# Register.net
KiCad netlist of a schematic drawn in EAGLE
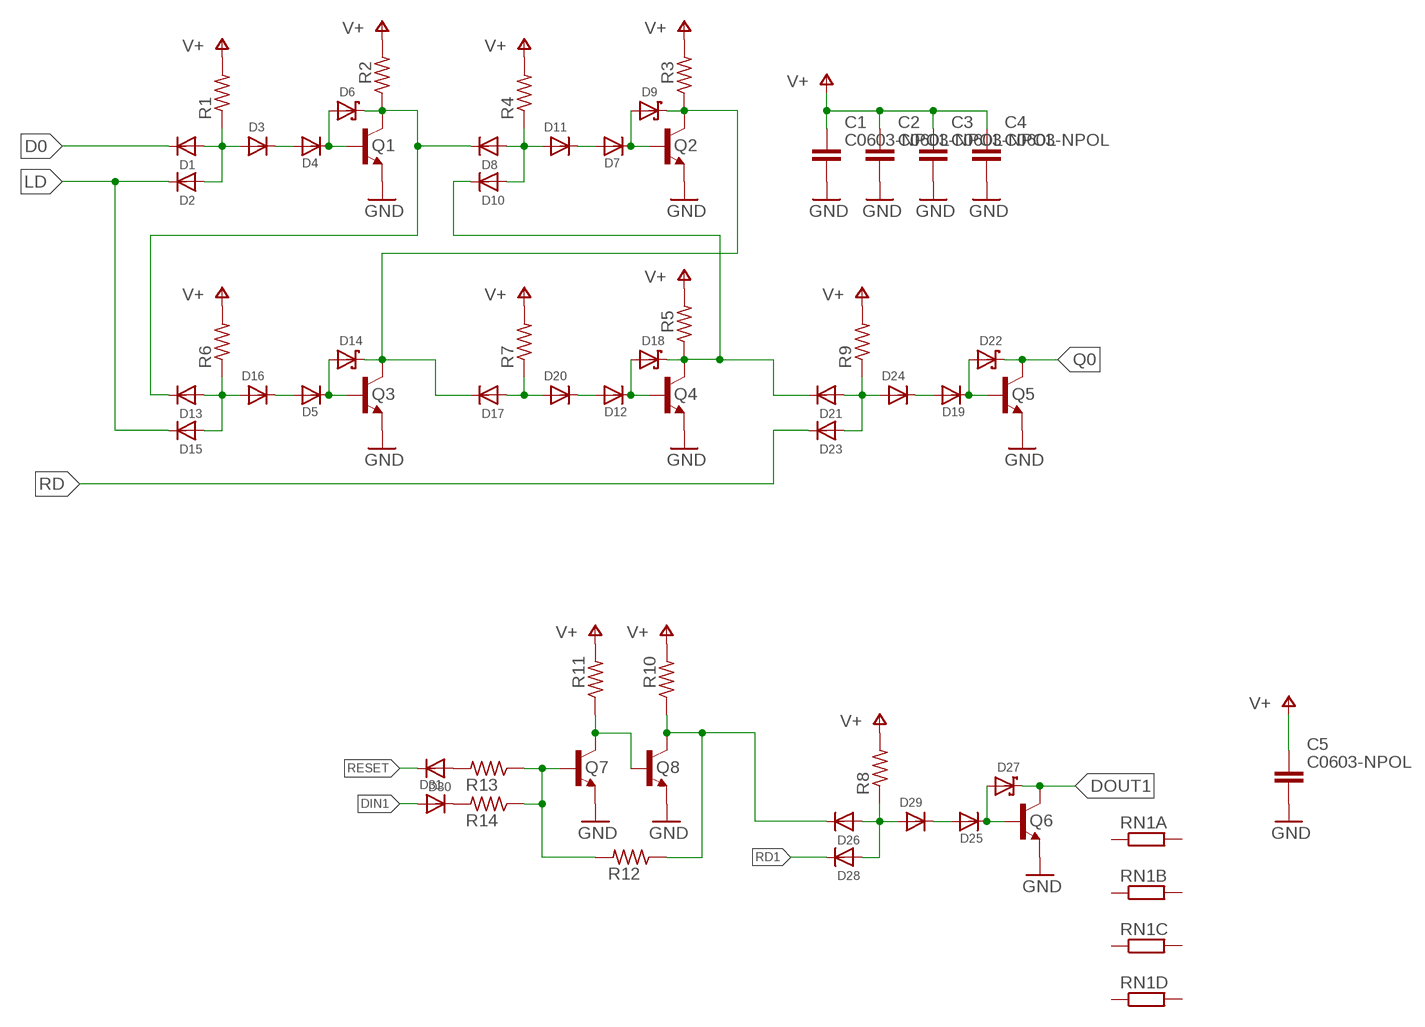
[diagram p0: schematic, sheet 1]

(export (version "E")
  (design (tool "Eeschema 10.0.6"))
  (components
    (comp (ref "C1")
      (value "C0603-NPOL")
      (footprint "eagle-import:C0603")
      (libsource (lib "eagle-import") (part "C0603-NPOL"))
    )
    (comp (ref "C2")
      (value "C0603-NPOL")
      (footprint "eagle-import:C0603")
      (libsource (lib "eagle-import") (part "C0603-NPOL"))
    )
    (comp (ref "C3")
      (value "C0603-NPOL")
      (footprint "eagle-import:C0603")
      (libsource (lib "eagle-import") (part "C0603-NPOL"))
    )
    (comp (ref "C4")
      (value "C0603-NPOL")
      (footprint "eagle-import:C0603")
      (libsource (lib "eagle-import") (part "C0603-NPOL"))
    )
    (comp (ref "C5")
      (value "C0603-NPOL")
      (footprint "eagle-import:C0603")
      (libsource (lib "eagle-import") (part "C0603-NPOL"))
    )
    (comp (ref "D1")
      (value "DIODE-SOD323")
      (footprint "eagle-import:SOD323F")
      (libsource (lib "eagle-import") (part "DIODE-SOD323"))
    )
    (comp (ref "D2")
      (value "DIODE-SOD323")
      (footprint "eagle-import:SOD323F")
      (libsource (lib "eagle-import") (part "DIODE-SOD323"))
    )
    (comp (ref "D3")
      (value "DIODE-SOD323")
      (footprint "eagle-import:SOD323F")
      (libsource (lib "eagle-import") (part "DIODE-SOD323"))
    )
    (comp (ref "D4")
      (value "DIODE-SOD323")
      (footprint "eagle-import:SOD323F")
      (libsource (lib "eagle-import") (part "DIODE-SOD323"))
    )
    (comp (ref "D5")
      (value "DIODE-SOD323")
      (footprint "eagle-import:SOD323F")
      (libsource (lib "eagle-import") (part "DIODE-SOD323"))
    )
    (comp (ref "D6")
      (value "SCHOTTKYSOT323")
      (footprint "eagle-import:SOT23")
      (libsource (lib "eagle-import") (part "SCHOTTKYSOT323"))
    )
    (comp (ref "D7")
      (value "DIODE-SOD323")
      (footprint "eagle-import:SOD323F")
      (libsource (lib "eagle-import") (part "DIODE-SOD323"))
    )
    (comp (ref "D8")
      (value "DIODE-SOD323")
      (footprint "eagle-import:SOD323F")
      (libsource (lib "eagle-import") (part "DIODE-SOD323"))
    )
    (comp (ref "D9")
      (value "SCHOTTKYSOT323")
      (footprint "eagle-import:SOT23")
      (libsource (lib "eagle-import") (part "SCHOTTKYSOT323"))
    )
    (comp (ref "D10")
      (value "DIODE-SOD323")
      (footprint "eagle-import:SOD323F")
      (libsource (lib "eagle-import") (part "DIODE-SOD323"))
    )
    (comp (ref "D11")
      (value "DIODE-SOD323")
      (footprint "eagle-import:SOD323F")
      (libsource (lib "eagle-import") (part "DIODE-SOD323"))
    )
    (comp (ref "D12")
      (value "DIODE-SOD323")
      (footprint "eagle-import:SOD323F")
      (libsource (lib "eagle-import") (part "DIODE-SOD323"))
    )
    (comp (ref "D13")
      (value "DIODE-SOD323")
      (footprint "eagle-import:SOD323F")
      (libsource (lib "eagle-import") (part "DIODE-SOD323"))
    )
    (comp (ref "D14")
      (value "SCHOTTKYSOT323")
      (footprint "eagle-import:SOT23")
      (libsource (lib "eagle-import") (part "SCHOTTKYSOT323"))
    )
    (comp (ref "D15")
      (value "DIODE-SOD323")
      (footprint "eagle-import:SOD323F")
      (libsource (lib "eagle-import") (part "DIODE-SOD323"))
    )
    (comp (ref "D16")
      (value "DIODE-SOD323")
      (footprint "eagle-import:SOD323F")
      (libsource (lib "eagle-import") (part "DIODE-SOD323"))
    )
    (comp (ref "D17")
      (value "DIODE-SOD323")
      (footprint "eagle-import:SOD323F")
      (libsource (lib "eagle-import") (part "DIODE-SOD323"))
    )
    (comp (ref "D18")
      (value "SCHOTTKYSOT323")
      (footprint "eagle-import:SOT23")
      (libsource (lib "eagle-import") (part "SCHOTTKYSOT323"))
    )
    (comp (ref "D19")
      (value "DIODE-SOD323")
      (footprint "eagle-import:SOD323F")
      (libsource (lib "eagle-import") (part "DIODE-SOD323"))
    )
    (comp (ref "D20")
      (value "DIODE-SOD323")
      (footprint "eagle-import:SOD323F")
      (libsource (lib "eagle-import") (part "DIODE-SOD323"))
    )
    (comp (ref "D21")
      (value "DIODE-SOD323")
      (footprint "eagle-import:SOD323F")
      (libsource (lib "eagle-import") (part "DIODE-SOD323"))
    )
    (comp (ref "D22")
      (value "SCHOTTKYSOT323")
      (footprint "eagle-import:SOT23")
      (libsource (lib "eagle-import") (part "SCHOTTKYSOT323"))
    )
    (comp (ref "D23")
      (value "DIODE-SOD323")
      (footprint "eagle-import:SOD323F")
      (libsource (lib "eagle-import") (part "DIODE-SOD323"))
    )
    (comp (ref "D24")
      (value "DIODE-SOD323")
      (footprint "eagle-import:SOD323F")
      (libsource (lib "eagle-import") (part "DIODE-SOD323"))
    )
    (comp (ref "D25")
      (value "DIODE-SOD323")
      (footprint "eagle-import:SOD323F")
      (libsource (lib "eagle-import") (part "DIODE-SOD323"))
    )
    (comp (ref "D26")
      (value "DIODE-SOD323")
      (footprint "eagle-import:SOD323F")
      (libsource (lib "eagle-import") (part "DIODE-SOD323"))
    )
    (comp (ref "D27")
      (value "SCHOTTKYSOT323")
      (footprint "eagle-import:SOT23")
      (libsource (lib "eagle-import") (part "SCHOTTKYSOT323"))
    )
    (comp (ref "D28")
      (value "DIODE-SOD323")
      (footprint "eagle-import:SOD323F")
      (libsource (lib "eagle-import") (part "DIODE-SOD323"))
    )
    (comp (ref "D29")
      (value "DIODE-SOD323")
      (footprint "eagle-import:SOD323F")
      (libsource (lib "eagle-import") (part "DIODE-SOD323"))
    )
    (comp (ref "D30")
      (value "DIODE-SOD323")
      (footprint "eagle-import:SOD323F")
      (libsource (lib "eagle-import") (part "DIODE-SOD323"))
    )
    (comp (ref "D31")
      (value "DIODE-SOD323")
      (footprint "eagle-import:SOD323F")
      (libsource (lib "eagle-import") (part "DIODE-SOD323"))
    )
    (comp (ref "Q1")
      (value "BC547-SOT23")
      (footprint "eagle-import:SOT23")
      (libsource (lib "eagle-import") (part "BC547-SOT23"))
    )
    (comp (ref "Q2")
      (value "BC547-SOT23")
      (footprint "eagle-import:SOT23")
      (libsource (lib "eagle-import") (part "BC547-SOT23"))
    )
    (comp (ref "Q3")
      (value "BC547-SOT23")
      (footprint "eagle-import:SOT23")
      (libsource (lib "eagle-import") (part "BC547-SOT23"))
    )
    (comp (ref "Q4")
      (value "BC547-SOT23")
      (footprint "eagle-import:SOT23")
      (libsource (lib "eagle-import") (part "BC547-SOT23"))
    )
    (comp (ref "Q5")
      (value "BC547-SOT23")
      (footprint "eagle-import:SOT23")
      (libsource (lib "eagle-import") (part "BC547-SOT23"))
    )
    (comp (ref "Q6")
      (value "BC547-SOT23")
      (footprint "eagle-import:SOT23")
      (libsource (lib "eagle-import") (part "BC547-SOT23"))
    )
    (comp (ref "Q7")
      (value "BC547-SOT23")
      (footprint "eagle-import:SOT23")
      (libsource (lib "eagle-import") (part "BC547-SOT23"))
    )
    (comp (ref "Q8")
      (value "BC547-SOT23")
      (footprint "eagle-import:SOT23")
      (libsource (lib "eagle-import") (part "BC547-SOT23"))
    )
    (comp (ref "R1")
      (value "470")
      (footprint "eagle-import:R0805")
      (libsource (lib "eagle-import") (part "R-0805"))
    )
    (comp (ref "R2")
      (value "150")
      (footprint "eagle-import:R0805")
      (libsource (lib "eagle-import") (part "R-0805"))
    )
    (comp (ref "R3")
      (value "150")
      (footprint "eagle-import:R0805")
      (libsource (lib "eagle-import") (part "R-0805"))
    )
    (comp (ref "R4")
      (value "470")
      (footprint "eagle-import:R0805")
      (libsource (lib "eagle-import") (part "R-0805"))
    )
    (comp (ref "R5")
      (value "150")
      (footprint "eagle-import:R0805")
      (libsource (lib "eagle-import") (part "R-0805"))
    )
    (comp (ref "R6")
      (value "470")
      (footprint "eagle-import:R0805")
      (libsource (lib "eagle-import") (part "R-0805"))
    )
    (comp (ref "R7")
      (value "470")
      (footprint "eagle-import:R0805")
      (libsource (lib "eagle-import") (part "R-0805"))
    )
    (comp (ref "R8")
      (value "470")
      (footprint "eagle-import:R0805")
      (libsource (lib "eagle-import") (part "R-0805"))
    )
    (comp (ref "R9")
      (value "470")
      (footprint "eagle-import:R0805")
      (libsource (lib "eagle-import") (part "R-0805"))
    )
    (comp (ref "R10")
      (value "150")
      (footprint "eagle-import:R0805")
      (libsource (lib "eagle-import") (part "R-0805"))
    )
    (comp (ref "R11")
      (value "150")
      (footprint "eagle-import:R0805")
      (libsource (lib "eagle-import") (part "R-0805"))
    )
    (comp (ref "R12")
      (value "150")
      (footprint "eagle-import:R0805")
      (libsource (lib "eagle-import") (part "R-0805"))
    )
    (comp (ref "R13")
      (value "150")
      (footprint "eagle-import:R0805")
      (libsource (lib "eagle-import") (part "R-0805"))
    )
    (comp (ref "R14")
      (value "150")
      (footprint "eagle-import:R0805")
      (libsource (lib "eagle-import") (part "R-0805"))
    )
    (comp (ref "RN1")
      (value "RESISTOR_ARRAY_4")
      (footprint "eagle-import:RN8P-4R-CRA06S")
      (libsource (lib "eagle-import") (part "RESISTOR_ARRAY_4"))
    )
  )
  (nets
    (net (code "1") (name "D0") (class "Default")
      (node (ref "D1") (pin "C") (pinfunction "C_C") (pintype "passive"))
    )
    (net (code "2") (name "DIN1") (class "Default")
      (node (ref "D31") (pin "A") (pinfunction "A_A") (pintype "passive"))
    )
    (net (code "3") (name "DOUT1") (class "Default")
      (node (ref "D27") (pin "3") (pinfunction "C_3") (pintype "passive"))
      (node (ref "Q6") (pin "3") (pinfunction "C_3") (pintype "passive"))
    )
    (net (code "4") (name "GND") (class "Default")
      (node (ref "C1") (pin "2") (pinfunction "2_2") (pintype "passive"))
      (node (ref "C2") (pin "2") (pinfunction "2_2") (pintype "passive"))
      (node (ref "C3") (pin "2") (pinfunction "2_2") (pintype "passive"))
      (node (ref "C4") (pin "2") (pinfunction "2_2") (pintype "passive"))
      (node (ref "C5") (pin "2") (pinfunction "2_2") (pintype "passive"))
      (node (ref "Q1") (pin "2") (pinfunction "E_2") (pintype "passive"))
      (node (ref "Q2") (pin "2") (pinfunction "E_2") (pintype "passive"))
      (node (ref "Q3") (pin "2") (pinfunction "E_2") (pintype "passive"))
      (node (ref "Q4") (pin "2") (pinfunction "E_2") (pintype "passive"))
      (node (ref "Q5") (pin "2") (pinfunction "E_2") (pintype "passive"))
      (node (ref "Q6") (pin "2") (pinfunction "E_2") (pintype "passive"))
      (node (ref "Q7") (pin "2") (pinfunction "E_2") (pintype "passive"))
      (node (ref "Q8") (pin "2") (pinfunction "E_2") (pintype "passive"))
    )
    (net (code "5") (name "LD") (class "Default")
      (node (ref "D15") (pin "C") (pinfunction "C_C") (pintype "passive"))
      (node (ref "D2") (pin "C") (pinfunction "C_C") (pintype "passive"))
    )
    (net (code "6") (name "Net-(D1-PadA)") (class "Default")
      (node (ref "D1") (pin "A") (pinfunction "A_A") (pintype "passive"))
      (node (ref "D2") (pin "A") (pinfunction "A_A") (pintype "passive"))
      (node (ref "D3") (pin "A") (pinfunction "A_A") (pintype "passive"))
      (node (ref "R1") (pin "1") (pinfunction "1_1") (pintype "passive"))
    )
    (net (code "7") (name "Net-(D3-PadC)") (class "Default")
      (node (ref "D3") (pin "C") (pinfunction "C_C") (pintype "passive"))
      (node (ref "D4") (pin "A") (pinfunction "A_A") (pintype "passive"))
    )
    (net (code "8") (name "Net-(D6-A)") (class "Default")
      (node (ref "D4") (pin "C") (pinfunction "C_C") (pintype "passive"))
      (node (ref "D6") (pin "1") (pinfunction "A_1") (pintype "passive"))
      (node (ref "Q1") (pin "1") (pinfunction "B_1") (pintype "passive"))
    )
    (net (code "9") (name "Net-(D6-C)") (class "Default")
      (node (ref "D13") (pin "C") (pinfunction "C_C") (pintype "passive"))
      (node (ref "D6") (pin "3") (pinfunction "C_3") (pintype "passive"))
      (node (ref "D8") (pin "C") (pinfunction "C_C") (pintype "passive"))
      (node (ref "Q1") (pin "3") (pinfunction "C_3") (pintype "passive"))
      (node (ref "R2") (pin "1") (pinfunction "1_1") (pintype "passive"))
    )
    (net (code "10") (name "Net-(D9-A)") (class "Default")
      (node (ref "D7") (pin "C") (pinfunction "C_C") (pintype "passive"))
      (node (ref "D9") (pin "1") (pinfunction "A_1") (pintype "passive"))
      (node (ref "Q2") (pin "1") (pinfunction "B_1") (pintype "passive"))
    )
    (net (code "11") (name "Net-(D10-PadA)") (class "Default")
      (node (ref "D10") (pin "A") (pinfunction "A_A") (pintype "passive"))
      (node (ref "D11") (pin "A") (pinfunction "A_A") (pintype "passive"))
      (node (ref "D8") (pin "A") (pinfunction "A_A") (pintype "passive"))
      (node (ref "R4") (pin "1") (pinfunction "1_1") (pintype "passive"))
    )
    (net (code "12") (name "Net-(D11-PadC)") (class "Default")
      (node (ref "D11") (pin "C") (pinfunction "C_C") (pintype "passive"))
      (node (ref "D7") (pin "A") (pinfunction "A_A") (pintype "passive"))
    )
    (net (code "13") (name "Net-(D12-PadA)") (class "Default")
      (node (ref "D12") (pin "A") (pinfunction "A_A") (pintype "passive"))
      (node (ref "D20") (pin "C") (pinfunction "C_C") (pintype "passive"))
    )
    (net (code "14") (name "Net-(D13-PadA)") (class "Default")
      (node (ref "D13") (pin "A") (pinfunction "A_A") (pintype "passive"))
      (node (ref "D15") (pin "A") (pinfunction "A_A") (pintype "passive"))
      (node (ref "D16") (pin "A") (pinfunction "A_A") (pintype "passive"))
      (node (ref "R6") (pin "1") (pinfunction "1_1") (pintype "passive"))
    )
    (net (code "15") (name "Net-(D14-A)") (class "Default")
      (node (ref "D14") (pin "1") (pinfunction "A_1") (pintype "passive"))
      (node (ref "D5") (pin "C") (pinfunction "C_C") (pintype "passive"))
      (node (ref "Q3") (pin "1") (pinfunction "B_1") (pintype "passive"))
    )
    (net (code "16") (name "Net-(D14-C)") (class "Default")
      (node (ref "D14") (pin "3") (pinfunction "C_3") (pintype "passive"))
      (node (ref "D17") (pin "C") (pinfunction "C_C") (pintype "passive"))
      (node (ref "D9") (pin "3") (pinfunction "C_3") (pintype "passive"))
      (node (ref "Q2") (pin "3") (pinfunction "C_3") (pintype "passive"))
      (node (ref "Q3") (pin "3") (pinfunction "C_3") (pintype "passive"))
      (node (ref "R3") (pin "1") (pinfunction "1_1") (pintype "passive"))
    )
    (net (code "17") (name "Net-(D16-PadC)") (class "Default")
      (node (ref "D16") (pin "C") (pinfunction "C_C") (pintype "passive"))
      (node (ref "D5") (pin "A") (pinfunction "A_A") (pintype "passive"))
    )
    (net (code "18") (name "Net-(D17-PadA)") (class "Default")
      (node (ref "D17") (pin "A") (pinfunction "A_A") (pintype "passive"))
      (node (ref "D20") (pin "A") (pinfunction "A_A") (pintype "passive"))
      (node (ref "R7") (pin "1") (pinfunction "1_1") (pintype "passive"))
    )
    (net (code "19") (name "Net-(D18-A)") (class "Default")
      (node (ref "D12") (pin "C") (pinfunction "C_C") (pintype "passive"))
      (node (ref "D18") (pin "1") (pinfunction "A_1") (pintype "passive"))
      (node (ref "Q4") (pin "1") (pinfunction "B_1") (pintype "passive"))
    )
    (net (code "20") (name "Net-(D18-C)") (class "Default")
      (node (ref "D10") (pin "C") (pinfunction "C_C") (pintype "passive"))
      (node (ref "D18") (pin "3") (pinfunction "C_3") (pintype "passive"))
      (node (ref "D21") (pin "C") (pinfunction "C_C") (pintype "passive"))
      (node (ref "Q4") (pin "3") (pinfunction "C_3") (pintype "passive"))
      (node (ref "R5") (pin "1") (pinfunction "1_1") (pintype "passive"))
    )
    (net (code "21") (name "Net-(D19-PadA)") (class "Default")
      (node (ref "D19") (pin "A") (pinfunction "A_A") (pintype "passive"))
      (node (ref "D24") (pin "C") (pinfunction "C_C") (pintype "passive"))
    )
    (net (code "22") (name "Net-(D21-PadA)") (class "Default")
      (node (ref "D21") (pin "A") (pinfunction "A_A") (pintype "passive"))
      (node (ref "D23") (pin "A") (pinfunction "A_A") (pintype "passive"))
      (node (ref "D24") (pin "A") (pinfunction "A_A") (pintype "passive"))
      (node (ref "R9") (pin "1") (pinfunction "1_1") (pintype "passive"))
    )
    (net (code "23") (name "Net-(D22-A)") (class "Default")
      (node (ref "D19") (pin "C") (pinfunction "C_C") (pintype "passive"))
      (node (ref "D22") (pin "1") (pinfunction "A_1") (pintype "passive"))
      (node (ref "Q5") (pin "1") (pinfunction "B_1") (pintype "passive"))
    )
    (net (code "24") (name "Net-(D25-PadA)") (class "Default")
      (node (ref "D25") (pin "A") (pinfunction "A_A") (pintype "passive"))
      (node (ref "D29") (pin "C") (pinfunction "C_C") (pintype "passive"))
    )
    (net (code "25") (name "Net-(D26-PadA)") (class "Default")
      (node (ref "D26") (pin "A") (pinfunction "A_A") (pintype "passive"))
      (node (ref "D28") (pin "A") (pinfunction "A_A") (pintype "passive"))
      (node (ref "D29") (pin "A") (pinfunction "A_A") (pintype "passive"))
      (node (ref "R8") (pin "1") (pinfunction "1_1") (pintype "passive"))
    )
    (net (code "26") (name "Net-(D27-A)") (class "Default")
      (node (ref "D25") (pin "C") (pinfunction "C_C") (pintype "passive"))
      (node (ref "D27") (pin "1") (pinfunction "A_1") (pintype "passive"))
      (node (ref "Q6") (pin "1") (pinfunction "B_1") (pintype "passive"))
    )
    (net (code "27") (name "Net-(D30-PadA)") (class "Default")
      (node (ref "D30") (pin "A") (pinfunction "A_A") (pintype "passive"))
      (node (ref "R13") (pin "2") (pinfunction "2_2") (pintype "passive"))
    )
    (net (code "28") (name "Net-(D31-PadC)") (class "Default")
      (node (ref "D31") (pin "C") (pinfunction "C_C") (pintype "passive"))
      (node (ref "R14") (pin "2") (pinfunction "2_2") (pintype "passive"))
    )
    (net (code "29") (name "Net-(Q7-B)") (class "Default")
      (node (ref "Q7") (pin "1") (pinfunction "B_1") (pintype "passive"))
      (node (ref "R12") (pin "2") (pinfunction "2_2") (pintype "passive"))
      (node (ref "R13") (pin "1") (pinfunction "1_1") (pintype "passive"))
      (node (ref "R14") (pin "1") (pinfunction "1_1") (pintype "passive"))
    )
    (net (code "30") (name "Net-(Q7-C)") (class "Default")
      (node (ref "Q7") (pin "3") (pinfunction "C_3") (pintype "passive"))
      (node (ref "Q8") (pin "1") (pinfunction "B_1") (pintype "passive"))
      (node (ref "R11") (pin "1") (pinfunction "1_1") (pintype "passive"))
    )
    (net (code "31") (name "Net-(Q8-C)") (class "Default")
      (node (ref "D26") (pin "C") (pinfunction "C_C") (pintype "passive"))
      (node (ref "Q8") (pin "3") (pinfunction "C_3") (pintype "passive"))
      (node (ref "R10") (pin "1") (pinfunction "1_1") (pintype "passive"))
      (node (ref "R12") (pin "1") (pinfunction "1_1") (pintype "passive"))
    )
    (net (code "32") (name "Q0") (class "Default")
      (node (ref "D22") (pin "3") (pinfunction "C_3") (pintype "passive"))
      (node (ref "Q5") (pin "3") (pinfunction "C_3") (pintype "passive"))
    )
    (net (code "33") (name "RD") (class "Default")
      (node (ref "D23") (pin "C") (pinfunction "C_C") (pintype "passive"))
    )
    (net (code "34") (name "RD1") (class "Default")
      (node (ref "D28") (pin "C") (pinfunction "C_C") (pintype "passive"))
    )
    (net (code "35") (name "RESET") (class "Default")
      (node (ref "D30") (pin "C") (pinfunction "C_C") (pintype "passive"))
    )
    (net (code "36") (name "V+") (class "Default")
      (node (ref "C1") (pin "1") (pinfunction "1_1") (pintype "passive"))
      (node (ref "C2") (pin "1") (pinfunction "1_1") (pintype "passive"))
      (node (ref "C3") (pin "1") (pinfunction "1_1") (pintype "passive"))
      (node (ref "C4") (pin "1") (pinfunction "1_1") (pintype "passive"))
      (node (ref "C5") (pin "1") (pinfunction "1_1") (pintype "passive"))
      (node (ref "R1") (pin "2") (pinfunction "2_2") (pintype "passive"))
      (node (ref "R10") (pin "2") (pinfunction "2_2") (pintype "passive"))
      (node (ref "R11") (pin "2") (pinfunction "2_2") (pintype "passive"))
      (node (ref "R2") (pin "2") (pinfunction "2_2") (pintype "passive"))
      (node (ref "R3") (pin "2") (pinfunction "2_2") (pintype "passive"))
      (node (ref "R4") (pin "2") (pinfunction "2_2") (pintype "passive"))
      (node (ref "R5") (pin "2") (pinfunction "2_2") (pintype "passive"))
      (node (ref "R6") (pin "2") (pinfunction "2_2") (pintype "passive"))
      (node (ref "R7") (pin "2") (pinfunction "2_2") (pintype "passive"))
      (node (ref "R8") (pin "2") (pinfunction "2_2") (pintype "passive"))
      (node (ref "R9") (pin "2") (pinfunction "2_2") (pintype "passive"))
    )
    (net (code "37") (name "unconnected-(RN1-Pad1)") (class "Default")
      (node (ref "RN1") (pin "1") (pinfunction "1_1") (pintype "passive"))
    )
    (net (code "38") (name "unconnected-(RN1A-2-Pad8)") (class "Default")
      (node (ref "RN1") (pin "8") (pinfunction "2_8") (pintype "passive"))
    )
    (net (code "39") (name "unconnected-(RN1B-1-Pad2)") (class "Default")
      (node (ref "RN1") (pin "2") (pinfunction "1_2") (pintype "passive"))
    )
    (net (code "40") (name "unconnected-(RN1B-2-Pad7)") (class "Default")
      (node (ref "RN1") (pin "7") (pinfunction "2_7") (pintype "passive"))
    )
    (net (code "41") (name "unconnected-(RN1C-1-Pad3)") (class "Default")
      (node (ref "RN1") (pin "3") (pinfunction "1_3") (pintype "passive"))
    )
    (net (code "42") (name "unconnected-(RN1C-2-Pad6)") (class "Default")
      (node (ref "RN1") (pin "6") (pinfunction "2_6") (pintype "passive"))
    )
    (net (code "43") (name "unconnected-(RN1D-1-Pad4)") (class "Default")
      (node (ref "RN1") (pin "4") (pinfunction "1_4") (pintype "passive"))
    )
    (net (code "44") (name "unconnected-(RN1D-2-Pad5)") (class "Default")
      (node (ref "RN1") (pin "5") (pinfunction "2_5") (pintype "passive"))
    )
  )
)
